# Mega_Shield-cjd.net
KiCad netlist of a schematic drawn in EAGLE
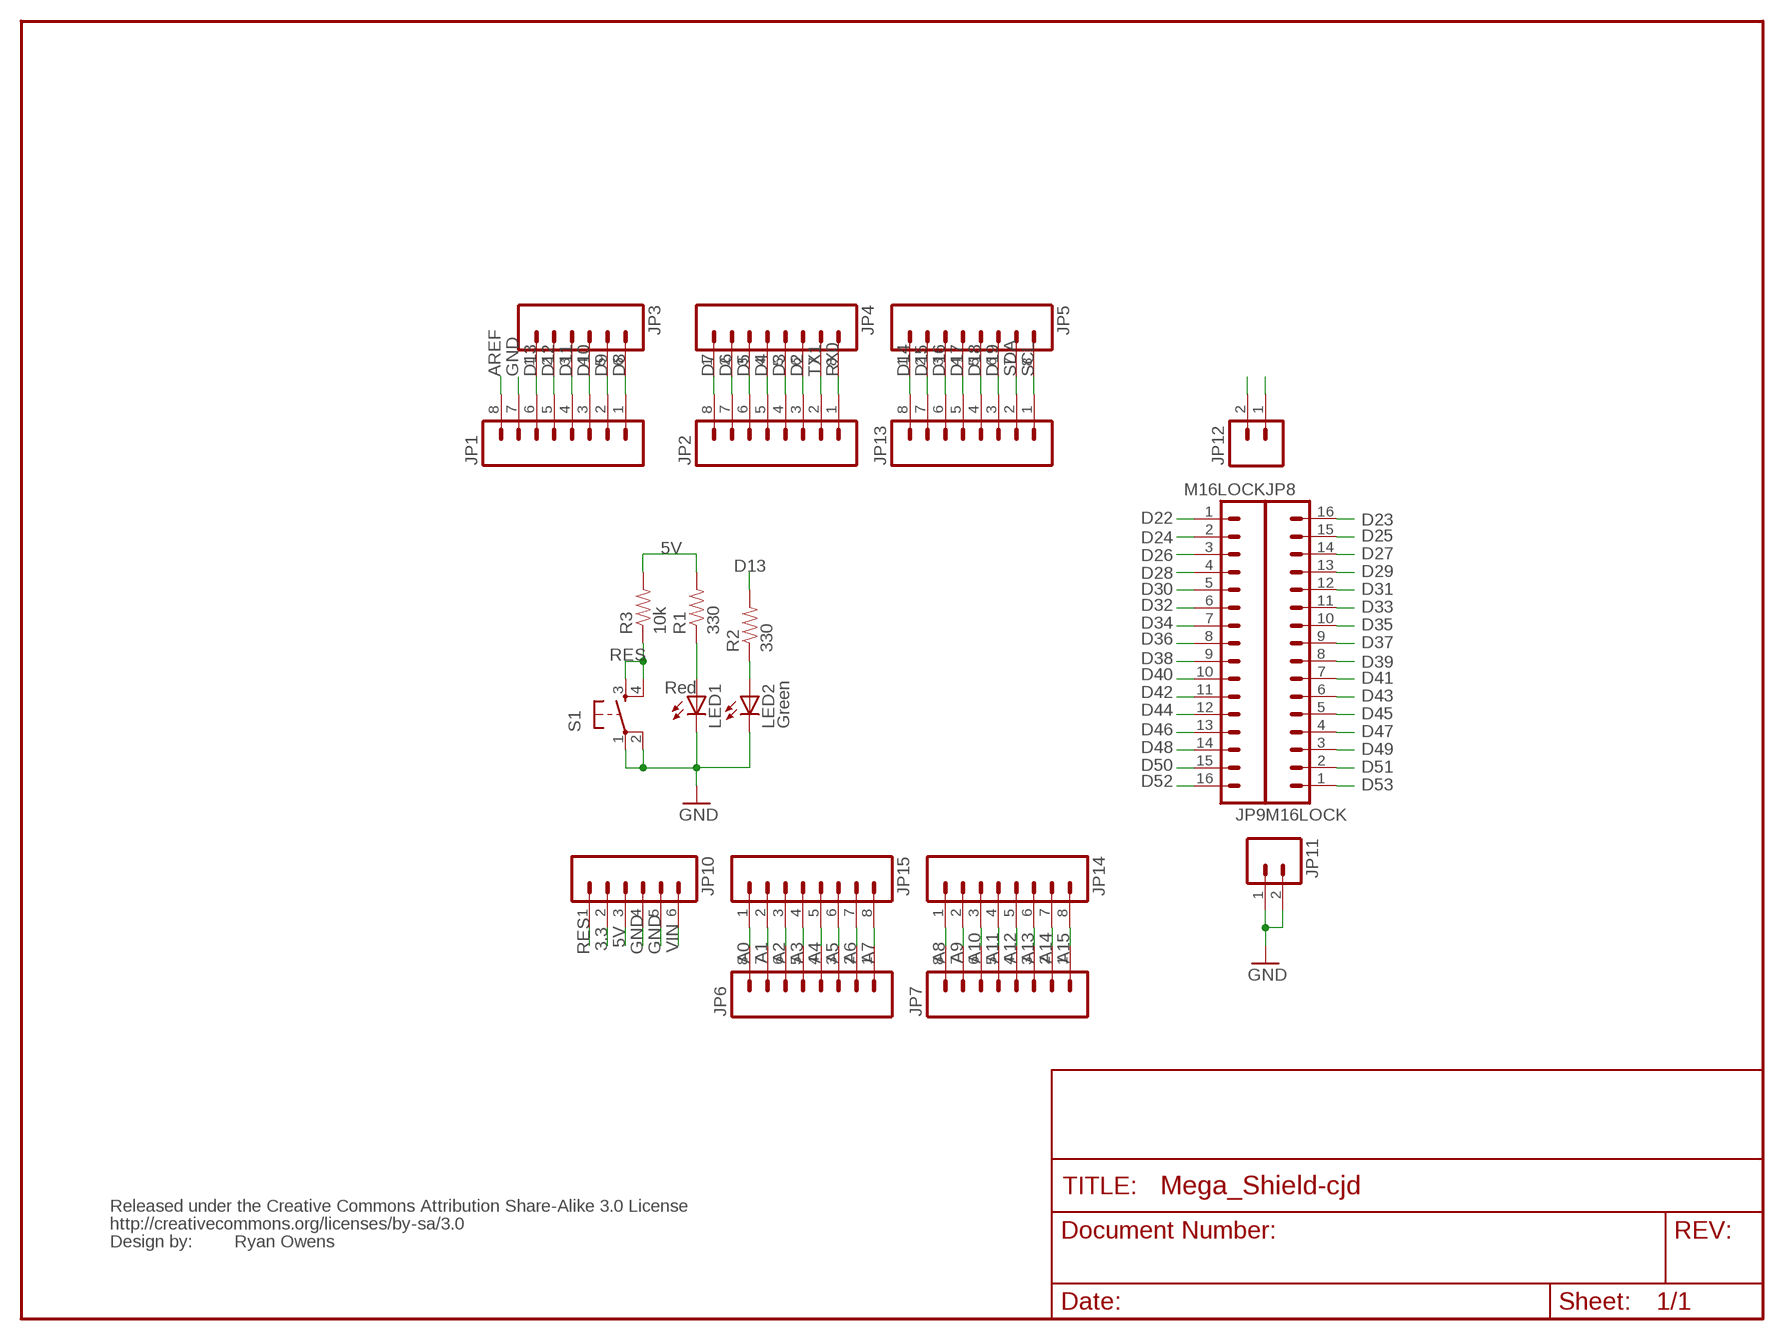
[diagram p0: schematic, sheet 1]

(export (version "E")
  (design (tool "Eeschema 10.0.6"))
  (components
    (comp (ref "JP1")
      (value "M081X08_LOCK_NO_PIN1")
      (footprint "eagle-import:1X08_LOCK_NO_PIN1")
      (libsource (lib "eagle-import") (part "M081X08_LOCK_NO_PIN1"))
    )
    (comp (ref "JP2")
      (value "M081X08_LOCK_NO_PIN1")
      (footprint "eagle-import:1X08_LOCK_NO_PIN1")
      (libsource (lib "eagle-import") (part "M081X08_LOCK_NO_PIN1"))
    )
    (comp (ref "JP3")
      (value "M06NO_SILK_FEMALE_PTH")
      (footprint "eagle-import:1X06_NO_SILK")
      (libsource (lib "eagle-import") (part "M06NO_SILK_FEMALE_PTH"))
    )
    (comp (ref "JP4")
      (value "M08NO_SILK_FEMALE_PTH")
      (footprint "eagle-import:1X08_NO_SILK")
      (libsource (lib "eagle-import") (part "M08NO_SILK_FEMALE_PTH"))
    )
    (comp (ref "JP5")
      (value "M08NO_SILK_FEMALE_PTH")
      (footprint "eagle-import:1X08_NO_SILK")
      (libsource (lib "eagle-import") (part "M08NO_SILK_FEMALE_PTH"))
    )
    (comp (ref "JP6")
      (value "M08NO_SILK_FEMALE_PTH")
      (footprint "eagle-import:1X08_NO_SILK")
      (libsource (lib "eagle-import") (part "M08NO_SILK_FEMALE_PTH"))
    )
    (comp (ref "JP7")
      (value "M08NO_SILK_FEMALE_PTH")
      (footprint "eagle-import:1X08_NO_SILK")
      (libsource (lib "eagle-import") (part "M08NO_SILK_FEMALE_PTH"))
    )
    (comp (ref "JP8")
      (value "M16LOCK")
      (footprint "eagle-import:1X16_LOCK")
      (libsource (lib "eagle-import") (part "M16LOCK"))
    )
    (comp (ref "JP9")
      (value "M16LOCK")
      (footprint "eagle-import:1X16_LOCK")
      (libsource (lib "eagle-import") (part "M16LOCK"))
    )
    (comp (ref "JP10")
      (value "M06LOCK")
      (footprint "eagle-import:1X06_LOCK")
      (libsource (lib "eagle-import") (part "M06LOCK"))
    )
    (comp (ref "JP11")
      (value "M02LOCK")
      (footprint "eagle-import:1X02_LOCK")
      (libsource (lib "eagle-import") (part "M02LOCK"))
    )
    (comp (ref "JP12")
      (value "M02LOCK")
      (footprint "eagle-import:1X02_LOCK")
      (libsource (lib "eagle-import") (part "M02LOCK"))
    )
    (comp (ref "JP13")
      (value "M081X08_LOCK_NO_PIN1")
      (footprint "eagle-import:1X08_LOCK_NO_PIN1")
      (libsource (lib "eagle-import") (part "M081X08_LOCK_NO_PIN1"))
    )
    (comp (ref "JP14")
      (value "M081X08_LOCK_NO_PIN1")
      (footprint "eagle-import:1X08_LOCK_NO_PIN1")
      (libsource (lib "eagle-import") (part "M081X08_LOCK_NO_PIN1"))
    )
    (comp (ref "JP15")
      (value "M081X08_LOCK_NO_PIN1")
      (footprint "eagle-import:1X08_LOCK_NO_PIN1")
      (libsource (lib "eagle-import") (part "M081X08_LOCK_NO_PIN1"))
    )
    (comp (ref "LED1")
      (value "Red")
      (footprint "eagle-import:LED5MM")
      (libsource (lib "eagle-import") (part "LED5MM"))
    )
    (comp (ref "LED2")
      (value "Green")
      (footprint "eagle-import:LED5MM")
      (libsource (lib "eagle-import") (part "LED5MM"))
    )
    (comp (ref "R1")
      (value "330")
      (footprint "eagle-import:AXIAL-0.3")
      (libsource (lib "eagle-import") (part "RESISTORPTH1"))
    )
    (comp (ref "R2")
      (value "330")
      (footprint "eagle-import:AXIAL-0.3")
      (libsource (lib "eagle-import") (part "RESISTORPTH1"))
    )
    (comp (ref "R3")
      (value "10k")
      (footprint "eagle-import:AXIAL-0.3")
      (libsource (lib "eagle-import") (part "RESISTORPTH1"))
    )
    (comp (ref "S1")
      (value "TAC_SWITCHPTH")
      (footprint "eagle-import:TACTILE-PTH")
      (libsource (lib "eagle-import") (part "TAC_SWITCHPTH"))
    )
    (comp (ref "U$2")
      (value "CREATIVE_COMMONS")
      (footprint "eagle-import:CREATIVE_COMMONS")
      (libsource (lib "eagle-import") (part "CREATIVE_COMMONS"))
    )
  )
  (nets
    (net (code "1") (name "/3.3") (class "Default")
      (node (ref "JP10") (pin "2") (pinfunction "2_2") (pintype "passive"))
    )
    (net (code "2") (name "/5V") (class "Default")
      (node (ref "JP10") (pin "3") (pinfunction "3_3") (pintype "passive"))
      (node (ref "R1") (pin "P$2") (pinfunction "2_P$2") (pintype "passive"))
      (node (ref "R3") (pin "P$2") (pinfunction "2_P$2") (pintype "passive"))
    )
    (net (code "3") (name "/5V@1") (class "Default")
      (node (ref "JP12") (pin "1") (pinfunction "1_1") (pintype "passive"))
      (node (ref "JP12") (pin "2") (pinfunction "2_2") (pintype "passive"))
    )
    (net (code "4") (name "/A0") (class "Default")
      (node (ref "JP15") (pin "1") (pinfunction "1_1") (pintype "passive"))
      (node (ref "JP6") (pin "8") (pinfunction "8_8") (pintype "passive"))
    )
    (net (code "5") (name "/A1") (class "Default")
      (node (ref "JP15") (pin "2") (pinfunction "2_2") (pintype "passive"))
      (node (ref "JP6") (pin "7") (pinfunction "7_7") (pintype "passive"))
    )
    (net (code "6") (name "/A2") (class "Default")
      (node (ref "JP15") (pin "3") (pinfunction "3_3") (pintype "passive"))
      (node (ref "JP6") (pin "6") (pinfunction "6_6") (pintype "passive"))
    )
    (net (code "7") (name "/A3") (class "Default")
      (node (ref "JP15") (pin "4") (pinfunction "4_4") (pintype "passive"))
      (node (ref "JP6") (pin "5") (pinfunction "5_5") (pintype "passive"))
    )
    (net (code "8") (name "/A4") (class "Default")
      (node (ref "JP15") (pin "5") (pinfunction "5_5") (pintype "passive"))
      (node (ref "JP6") (pin "4") (pinfunction "4_4") (pintype "passive"))
    )
    (net (code "9") (name "/A5") (class "Default")
      (node (ref "JP15") (pin "6") (pinfunction "6_6") (pintype "passive"))
      (node (ref "JP6") (pin "3") (pinfunction "3_3") (pintype "passive"))
    )
    (net (code "10") (name "/A6") (class "Default")
      (node (ref "JP15") (pin "7") (pinfunction "7_7") (pintype "passive"))
      (node (ref "JP6") (pin "2") (pinfunction "2_2") (pintype "passive"))
    )
    (net (code "11") (name "/A7") (class "Default")
      (node (ref "JP15") (pin "8") (pinfunction "8_8") (pintype "passive"))
      (node (ref "JP6") (pin "1") (pinfunction "1_1") (pintype "passive"))
    )
    (net (code "12") (name "/A8") (class "Default")
      (node (ref "JP14") (pin "1") (pinfunction "1_1") (pintype "passive"))
      (node (ref "JP7") (pin "8") (pinfunction "8_8") (pintype "passive"))
    )
    (net (code "13") (name "/A9") (class "Default")
      (node (ref "JP14") (pin "2") (pinfunction "2_2") (pintype "passive"))
      (node (ref "JP7") (pin "7") (pinfunction "7_7") (pintype "passive"))
    )
    (net (code "14") (name "/A10") (class "Default")
      (node (ref "JP14") (pin "3") (pinfunction "3_3") (pintype "passive"))
      (node (ref "JP7") (pin "6") (pinfunction "6_6") (pintype "passive"))
    )
    (net (code "15") (name "/A11") (class "Default")
      (node (ref "JP14") (pin "4") (pinfunction "4_4") (pintype "passive"))
      (node (ref "JP7") (pin "5") (pinfunction "5_5") (pintype "passive"))
    )
    (net (code "16") (name "/A12") (class "Default")
      (node (ref "JP14") (pin "5") (pinfunction "5_5") (pintype "passive"))
      (node (ref "JP7") (pin "4") (pinfunction "4_4") (pintype "passive"))
    )
    (net (code "17") (name "/A13") (class "Default")
      (node (ref "JP14") (pin "6") (pinfunction "6_6") (pintype "passive"))
      (node (ref "JP7") (pin "3") (pinfunction "3_3") (pintype "passive"))
    )
    (net (code "18") (name "/A14") (class "Default")
      (node (ref "JP14") (pin "7") (pinfunction "7_7") (pintype "passive"))
      (node (ref "JP7") (pin "2") (pinfunction "2_2") (pintype "passive"))
    )
    (net (code "19") (name "/A15") (class "Default")
      (node (ref "JP14") (pin "8") (pinfunction "8_8") (pintype "passive"))
      (node (ref "JP7") (pin "1") (pinfunction "1_1") (pintype "passive"))
    )
    (net (code "20") (name "/AREF") (class "Default")
      (node (ref "JP1") (pin "8") (pinfunction "8_8") (pintype "passive"))
    )
    (net (code "21") (name "/D2") (class "Default")
      (node (ref "JP2") (pin "3") (pinfunction "3_3") (pintype "passive"))
      (node (ref "JP4") (pin "6") (pinfunction "6_6") (pintype "passive"))
    )
    (net (code "22") (name "/D3") (class "Default")
      (node (ref "JP2") (pin "4") (pinfunction "4_4") (pintype "passive"))
      (node (ref "JP4") (pin "5") (pinfunction "5_5") (pintype "passive"))
    )
    (net (code "23") (name "/D4") (class "Default")
      (node (ref "JP2") (pin "5") (pinfunction "5_5") (pintype "passive"))
      (node (ref "JP4") (pin "4") (pinfunction "4_4") (pintype "passive"))
    )
    (net (code "24") (name "/D5") (class "Default")
      (node (ref "JP2") (pin "6") (pinfunction "6_6") (pintype "passive"))
      (node (ref "JP4") (pin "3") (pinfunction "3_3") (pintype "passive"))
    )
    (net (code "25") (name "/D6") (class "Default")
      (node (ref "JP2") (pin "7") (pinfunction "7_7") (pintype "passive"))
      (node (ref "JP4") (pin "2") (pinfunction "2_2") (pintype "passive"))
    )
    (net (code "26") (name "/D7") (class "Default")
      (node (ref "JP2") (pin "8") (pinfunction "8_8") (pintype "passive"))
      (node (ref "JP4") (pin "1") (pinfunction "1_1") (pintype "passive"))
    )
    (net (code "27") (name "/D8") (class "Default")
      (node (ref "JP1") (pin "1") (pinfunction "1_1") (pintype "passive"))
      (node (ref "JP3") (pin "6") (pinfunction "6_6") (pintype "passive"))
    )
    (net (code "28") (name "/D9") (class "Default")
      (node (ref "JP1") (pin "2") (pinfunction "2_2") (pintype "passive"))
      (node (ref "JP3") (pin "5") (pinfunction "5_5") (pintype "passive"))
    )
    (net (code "29") (name "/D10") (class "Default")
      (node (ref "JP1") (pin "3") (pinfunction "3_3") (pintype "passive"))
      (node (ref "JP3") (pin "4") (pinfunction "4_4") (pintype "passive"))
    )
    (net (code "30") (name "/D11") (class "Default")
      (node (ref "JP1") (pin "4") (pinfunction "4_4") (pintype "passive"))
      (node (ref "JP3") (pin "3") (pinfunction "3_3") (pintype "passive"))
    )
    (net (code "31") (name "/D12") (class "Default")
      (node (ref "JP1") (pin "5") (pinfunction "5_5") (pintype "passive"))
      (node (ref "JP3") (pin "2") (pinfunction "2_2") (pintype "passive"))
    )
    (net (code "32") (name "/D13") (class "Default")
      (node (ref "JP1") (pin "6") (pinfunction "6_6") (pintype "passive"))
      (node (ref "JP3") (pin "1") (pinfunction "1_1") (pintype "passive"))
      (node (ref "R2") (pin "P$2") (pinfunction "2_P$2") (pintype "passive"))
    )
    (net (code "33") (name "/D14") (class "Default")
      (node (ref "JP13") (pin "8") (pinfunction "8_8") (pintype "passive"))
      (node (ref "JP5") (pin "1") (pinfunction "1_1") (pintype "passive"))
    )
    (net (code "34") (name "/D15") (class "Default")
      (node (ref "JP13") (pin "7") (pinfunction "7_7") (pintype "passive"))
      (node (ref "JP5") (pin "2") (pinfunction "2_2") (pintype "passive"))
    )
    (net (code "35") (name "/D16") (class "Default")
      (node (ref "JP13") (pin "6") (pinfunction "6_6") (pintype "passive"))
      (node (ref "JP5") (pin "3") (pinfunction "3_3") (pintype "passive"))
    )
    (net (code "36") (name "/D17") (class "Default")
      (node (ref "JP13") (pin "5") (pinfunction "5_5") (pintype "passive"))
      (node (ref "JP5") (pin "4") (pinfunction "4_4") (pintype "passive"))
    )
    (net (code "37") (name "/D18") (class "Default")
      (node (ref "JP13") (pin "4") (pinfunction "4_4") (pintype "passive"))
      (node (ref "JP5") (pin "5") (pinfunction "5_5") (pintype "passive"))
    )
    (net (code "38") (name "/D19") (class "Default")
      (node (ref "JP13") (pin "3") (pinfunction "3_3") (pintype "passive"))
      (node (ref "JP5") (pin "6") (pinfunction "6_6") (pintype "passive"))
    )
    (net (code "39") (name "/D22") (class "Default")
      (node (ref "JP9") (pin "1") (pinfunction "1_1") (pintype "passive"))
    )
    (net (code "40") (name "/D23") (class "Default")
      (node (ref "JP8") (pin "16") (pinfunction "16_16") (pintype "passive"))
    )
    (net (code "41") (name "/D24") (class "Default")
      (node (ref "JP9") (pin "2") (pinfunction "2_2") (pintype "passive"))
    )
    (net (code "42") (name "/D25") (class "Default")
      (node (ref "JP8") (pin "15") (pinfunction "15_15") (pintype "passive"))
    )
    (net (code "43") (name "/D26") (class "Default")
      (node (ref "JP9") (pin "3") (pinfunction "3_3") (pintype "passive"))
    )
    (net (code "44") (name "/D27") (class "Default")
      (node (ref "JP8") (pin "14") (pinfunction "14_14") (pintype "passive"))
    )
    (net (code "45") (name "/D28") (class "Default")
      (node (ref "JP9") (pin "4") (pinfunction "4_4") (pintype "passive"))
    )
    (net (code "46") (name "/D29") (class "Default")
      (node (ref "JP8") (pin "13") (pinfunction "13_13") (pintype "passive"))
    )
    (net (code "47") (name "/D30") (class "Default")
      (node (ref "JP9") (pin "5") (pinfunction "5_5") (pintype "passive"))
    )
    (net (code "48") (name "/D31") (class "Default")
      (node (ref "JP8") (pin "12") (pinfunction "12_12") (pintype "passive"))
    )
    (net (code "49") (name "/D32") (class "Default")
      (node (ref "JP9") (pin "6") (pinfunction "6_6") (pintype "passive"))
    )
    (net (code "50") (name "/D33") (class "Default")
      (node (ref "JP8") (pin "11") (pinfunction "11_11") (pintype "passive"))
    )
    (net (code "51") (name "/D34") (class "Default")
      (node (ref "JP9") (pin "7") (pinfunction "7_7") (pintype "passive"))
    )
    (net (code "52") (name "/D35") (class "Default")
      (node (ref "JP8") (pin "10") (pinfunction "10_10") (pintype "passive"))
    )
    (net (code "53") (name "/D36") (class "Default")
      (node (ref "JP9") (pin "8") (pinfunction "8_8") (pintype "passive"))
    )
    (net (code "54") (name "/D37") (class "Default")
      (node (ref "JP8") (pin "9") (pinfunction "9_9") (pintype "passive"))
    )
    (net (code "55") (name "/D38") (class "Default")
      (node (ref "JP9") (pin "9") (pinfunction "9_9") (pintype "passive"))
    )
    (net (code "56") (name "/D39") (class "Default")
      (node (ref "JP8") (pin "8") (pinfunction "8_8") (pintype "passive"))
    )
    (net (code "57") (name "/D40") (class "Default")
      (node (ref "JP9") (pin "10") (pinfunction "10_10") (pintype "passive"))
    )
    (net (code "58") (name "/D41") (class "Default")
      (node (ref "JP8") (pin "7") (pinfunction "7_7") (pintype "passive"))
    )
    (net (code "59") (name "/D42") (class "Default")
      (node (ref "JP9") (pin "11") (pinfunction "11_11") (pintype "passive"))
    )
    (net (code "60") (name "/D43") (class "Default")
      (node (ref "JP8") (pin "6") (pinfunction "6_6") (pintype "passive"))
    )
    (net (code "61") (name "/D44") (class "Default")
      (node (ref "JP9") (pin "12") (pinfunction "12_12") (pintype "passive"))
    )
    (net (code "62") (name "/D45") (class "Default")
      (node (ref "JP8") (pin "5") (pinfunction "5_5") (pintype "passive"))
    )
    (net (code "63") (name "/D46") (class "Default")
      (node (ref "JP9") (pin "13") (pinfunction "13_13") (pintype "passive"))
    )
    (net (code "64") (name "/D47") (class "Default")
      (node (ref "JP8") (pin "4") (pinfunction "4_4") (pintype "passive"))
    )
    (net (code "65") (name "/D48") (class "Default")
      (node (ref "JP9") (pin "14") (pinfunction "14_14") (pintype "passive"))
    )
    (net (code "66") (name "/D49") (class "Default")
      (node (ref "JP8") (pin "3") (pinfunction "3_3") (pintype "passive"))
    )
    (net (code "67") (name "/D50") (class "Default")
      (node (ref "JP9") (pin "15") (pinfunction "15_15") (pintype "passive"))
    )
    (net (code "68") (name "/D51") (class "Default")
      (node (ref "JP8") (pin "2") (pinfunction "2_2") (pintype "passive"))
    )
    (net (code "69") (name "/D52") (class "Default")
      (node (ref "JP9") (pin "16") (pinfunction "16_16") (pintype "passive"))
    )
    (net (code "70") (name "/D53") (class "Default")
      (node (ref "JP8") (pin "1") (pinfunction "1_1") (pintype "passive"))
    )
    (net (code "71") (name "/RES") (class "Default")
      (node (ref "JP10") (pin "1") (pinfunction "1_1") (pintype "passive"))
      (node (ref "R3") (pin "P$1") (pinfunction "1_P$1") (pintype "passive"))
      (node (ref "S1") (pin "3") (pinfunction "3_3") (pintype "passive"))
      (node (ref "S1") (pin "4") (pinfunction "4_4") (pintype "passive"))
    )
    (net (code "72") (name "/RX0") (class "Default")
      (node (ref "JP2") (pin "1") (pinfunction "1_1") (pintype "passive"))
      (node (ref "JP4") (pin "8") (pinfunction "8_8") (pintype "passive"))
    )
    (net (code "73") (name "/SCL") (class "Default")
      (node (ref "JP13") (pin "1") (pinfunction "1_1") (pintype "passive"))
      (node (ref "JP5") (pin "8") (pinfunction "8_8") (pintype "passive"))
    )
    (net (code "74") (name "/SDA") (class "Default")
      (node (ref "JP13") (pin "2") (pinfunction "2_2") (pintype "passive"))
      (node (ref "JP5") (pin "7") (pinfunction "7_7") (pintype "passive"))
    )
    (net (code "75") (name "/TX1") (class "Default")
      (node (ref "JP2") (pin "2") (pinfunction "2_2") (pintype "passive"))
      (node (ref "JP4") (pin "7") (pinfunction "7_7") (pintype "passive"))
    )
    (net (code "76") (name "/VIN") (class "Default")
      (node (ref "JP10") (pin "6") (pinfunction "6_6") (pintype "passive"))
    )
    (net (code "77") (name "GND") (class "Default")
      (node (ref "JP1") (pin "7") (pinfunction "7_7") (pintype "passive"))
      (node (ref "JP10") (pin "4") (pinfunction "4_4") (pintype "passive"))
      (node (ref "JP10") (pin "5") (pinfunction "5_5") (pintype "passive"))
      (node (ref "JP11") (pin "1") (pinfunction "1_1") (pintype "passive"))
      (node (ref "JP11") (pin "2") (pinfunction "2_2") (pintype "passive"))
      (node (ref "LED1") (pin "K") (pinfunction "C_K") (pintype "passive"))
      (node (ref "LED2") (pin "K") (pinfunction "C_K") (pintype "passive"))
      (node (ref "S1") (pin "1") (pinfunction "1_1") (pintype "passive"))
      (node (ref "S1") (pin "2") (pinfunction "2_2") (pintype "passive"))
    )
    (net (code "78") (name "Net-(R1-1)") (class "Default")
      (node (ref "LED1") (pin "A") (pinfunction "A_A") (pintype "passive"))
      (node (ref "R1") (pin "P$1") (pinfunction "1_P$1") (pintype "passive"))
    )
    (net (code "79") (name "Net-(R2-1)") (class "Default")
      (node (ref "LED2") (pin "A") (pinfunction "A_A") (pintype "passive"))
      (node (ref "R2") (pin "P$1") (pinfunction "1_P$1") (pintype "passive"))
    )
  )
)
